# eMMC.net
KiCad netlist of a schematic drawn in Altium Designer
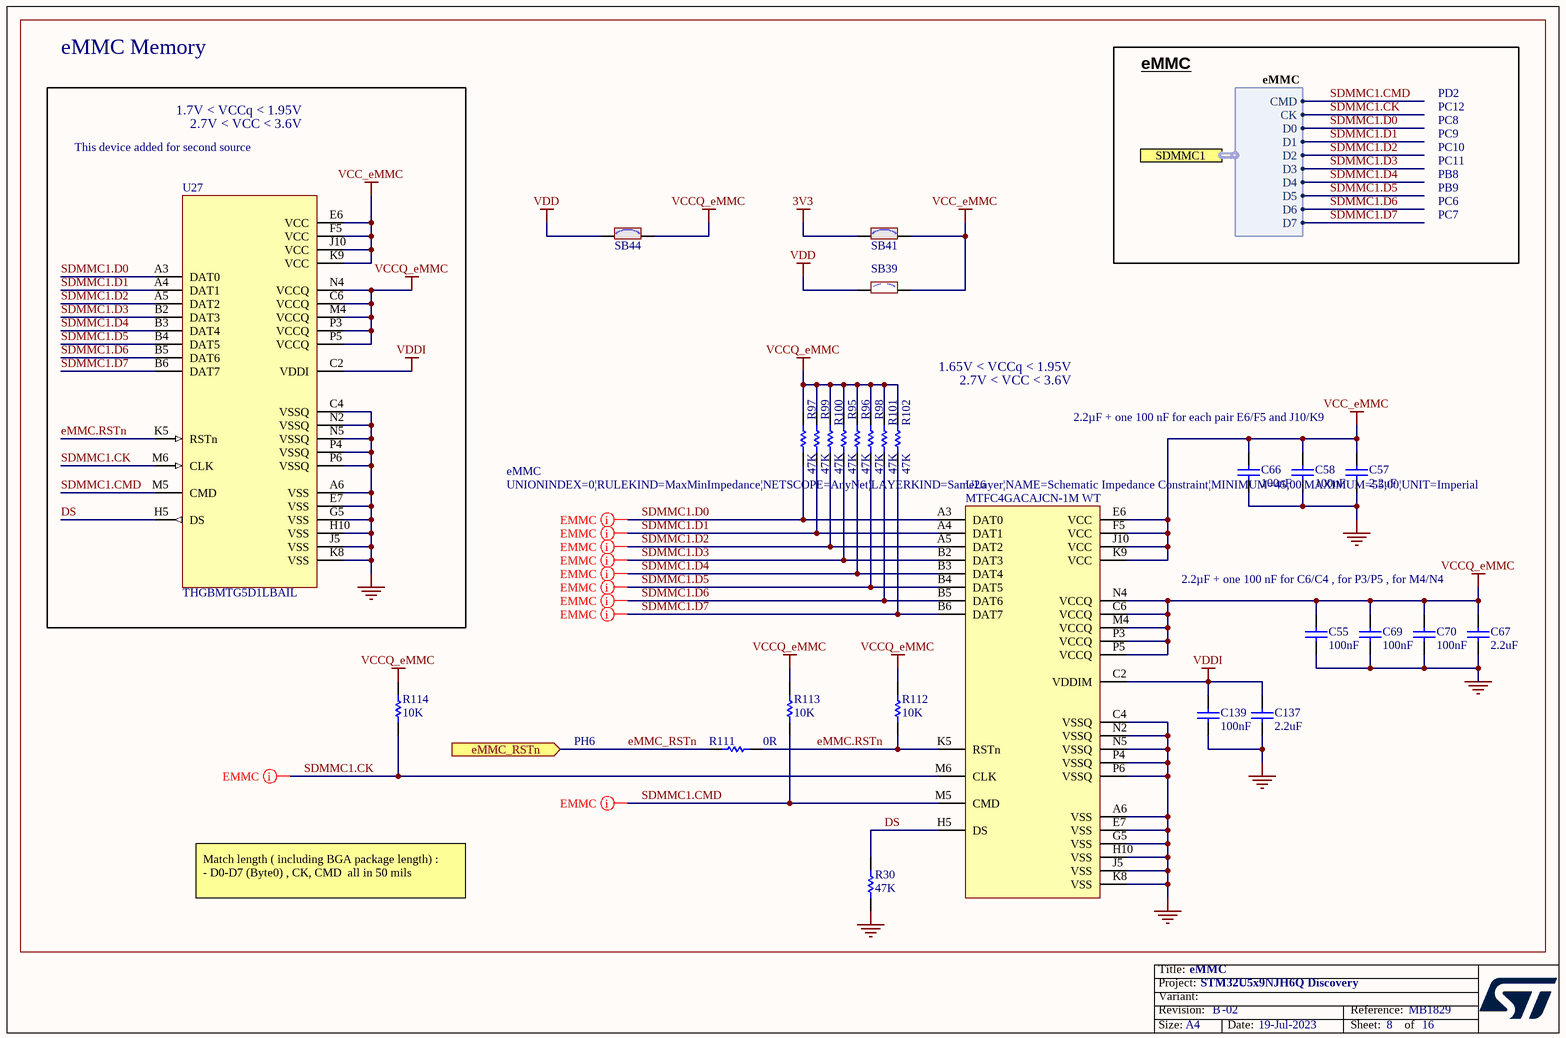
[diagram p0: eMMC.SchDoc]

(export (version "E")
  (design (tool "Eeschema 10.0.6"))
  (components
    (comp (ref "C55")
      (value "100nF")
      (footprint "MCD_PARTS:C0402")
      (description "Capacitor, MLCC, 100nF, 16V, X7R, +/-10%, 0402, T=0.5mm")
      (fields
        (field (name "INTERNAL_PART_NUMBER") "MCD-00006")
        (field (name "MANUFACTURER_PART_NUMBER") "CC0402KRX7R7BB104")
      )
      (libsource (lib "MCD_PARTS_database") (part "Capacitor"))
    )
    (comp (ref "C57")
      (value "2.2uF")
      (footprint "MCD_PARTS:C0603")
      (description "Capacitor, MLCC, 2.2uF, 10V, X5R, +/- 10%, 0603, T=0.8mm")
      (fields
        (field (name "INTERNAL_PART_NUMBER") "MCD-00012")
        (field (name "MANUFACTURER_PART_NUMBER") "CC0603KRX5R6BB225")
      )
      (libsource (lib "MCD_PARTS_database") (part "Capacitor"))
    )
    (comp (ref "C58")
      (value "100nF")
      (footprint "MCD_PARTS:C0402")
      (description "Capacitor, MLCC, 100nF, 16V, X7R, +/-10%, 0402, T=0.5mm")
      (fields
        (field (name "INTERNAL_PART_NUMBER") "MCD-00006")
        (field (name "MANUFACTURER_PART_NUMBER") "CC0402KRX7R7BB104")
      )
      (libsource (lib "MCD_PARTS_database") (part "Capacitor"))
    )
    (comp (ref "C66")
      (value "100nF")
      (footprint "MCD_PARTS:C0402")
      (description "Capacitor, MLCC, 100nF, 16V, X7R, +/-10%, 0402, T=0.5mm")
      (fields
        (field (name "INTERNAL_PART_NUMBER") "MCD-00006")
        (field (name "MANUFACTURER_PART_NUMBER") "CC0402KRX7R7BB104")
      )
      (libsource (lib "MCD_PARTS_database") (part "Capacitor"))
    )
    (comp (ref "C67")
      (value "2.2uF")
      (footprint "MCD_PARTS:C0603")
      (description "Capacitor, MLCC, 2.2uF, 10V, X5R, +/- 10%, 0603, T=0.8mm")
      (fields
        (field (name "INTERNAL_PART_NUMBER") "MCD-00012")
        (field (name "MANUFACTURER_PART_NUMBER") "CC0603KRX5R6BB225")
      )
      (libsource (lib "MCD_PARTS_database") (part "Capacitor"))
    )
    (comp (ref "C69")
      (value "100nF")
      (footprint "MCD_PARTS:C0402")
      (description "Capacitor, MLCC, 100nF, 16V, X7R, +/-10%, 0402, T=0.5mm")
      (fields
        (field (name "INTERNAL_PART_NUMBER") "MCD-00006")
        (field (name "MANUFACTURER_PART_NUMBER") "CC0402KRX7R7BB104")
      )
      (libsource (lib "MCD_PARTS_database") (part "Capacitor"))
    )
    (comp (ref "C70")
      (value "100nF")
      (footprint "MCD_PARTS:C0402")
      (description "Capacitor, MLCC, 100nF, 16V, X7R, +/-10%, 0402, T=0.5mm")
      (fields
        (field (name "INTERNAL_PART_NUMBER") "MCD-00006")
        (field (name "MANUFACTURER_PART_NUMBER") "CC0402KRX7R7BB104")
      )
      (libsource (lib "MCD_PARTS_database") (part "Capacitor"))
    )
    (comp (ref "C137")
      (value "2.2uF")
      (footprint "MCD_PARTS:C0603")
      (description "Capacitor, MLCC, 2.2uF, 10V, X5R, +/- 10%, 0603, T=0.8mm")
      (fields
        (field (name "INTERNAL_PART_NUMBER") "MCD-00012")
        (field (name "MANUFACTURER_PART_NUMBER") "CC0603KRX5R6BB225")
      )
      (libsource (lib "MCD_PARTS_database") (part "Capacitor"))
    )
    (comp (ref "C139")
      (value "100nF")
      (footprint "MCD_PARTS:C0402")
      (description "Capacitor, MLCC, 100nF, 16V, X7R, +/-10%, 0402, T=0.5mm")
      (fields
        (field (name "INTERNAL_PART_NUMBER") "MCD-00006")
        (field (name "MANUFACTURER_PART_NUMBER") "CC0402KRX7R7BB104")
      )
      (libsource (lib "MCD_PARTS_database") (part "Capacitor"))
    )
    (comp (ref "R30")
      (value "47K")
      (footprint "MCD_PARTS:R0402")
      (description "Resistor, 47K, 0402, +/-1%, 1/16W")
      (fields
        (field (name "INTERNAL_PART_NUMBER") "MCD-00063")
        (field (name "MANUFACTURER_PART_NUMBER") "RC0402FR-0747KL")
      )
      (libsource (lib "MCD_PARTS_database") (part "Resistor"))
    )
    (comp (ref "R95")
      (value "47K")
      (footprint "MCD_PARTS:R0402")
      (description "Resistor, 47K, 0402, +/-1%, 1/16W")
      (fields
        (field (name "INTERNAL_PART_NUMBER") "MCD-00063")
        (field (name "MANUFACTURER_PART_NUMBER") "RC0402FR-0747KL")
      )
      (libsource (lib "MCD_PARTS_database") (part "Resistor"))
    )
    (comp (ref "R96")
      (value "47K")
      (footprint "MCD_PARTS:R0402")
      (description "Resistor, 47K, 0402, +/-1%, 1/16W")
      (fields
        (field (name "INTERNAL_PART_NUMBER") "MCD-00063")
        (field (name "MANUFACTURER_PART_NUMBER") "RC0402FR-0747KL")
      )
      (libsource (lib "MCD_PARTS_database") (part "Resistor"))
    )
    (comp (ref "R97")
      (value "47K")
      (footprint "MCD_PARTS:R0402")
      (description "Resistor, 47K, 0402, +/-1%, 1/16W")
      (fields
        (field (name "INTERNAL_PART_NUMBER") "MCD-00063")
        (field (name "MANUFACTURER_PART_NUMBER") "RC0402FR-0747KL")
      )
      (libsource (lib "MCD_PARTS_database") (part "Resistor"))
    )
    (comp (ref "R98")
      (value "47K")
      (footprint "MCD_PARTS:R0402")
      (description "Resistor, 47K, 0402, +/-1%, 1/16W")
      (fields
        (field (name "INTERNAL_PART_NUMBER") "MCD-00063")
        (field (name "MANUFACTURER_PART_NUMBER") "RC0402FR-0747KL")
      )
      (libsource (lib "MCD_PARTS_database") (part "Resistor"))
    )
    (comp (ref "R99")
      (value "47K")
      (footprint "MCD_PARTS:R0402")
      (description "Resistor, 47K, 0402, +/-1%, 1/16W")
      (fields
        (field (name "INTERNAL_PART_NUMBER") "MCD-00063")
        (field (name "MANUFACTURER_PART_NUMBER") "RC0402FR-0747KL")
      )
      (libsource (lib "MCD_PARTS_database") (part "Resistor"))
    )
    (comp (ref "R100")
      (value "47K")
      (footprint "MCD_PARTS:R0402")
      (description "Resistor, 47K, 0402, +/-1%, 1/16W")
      (fields
        (field (name "INTERNAL_PART_NUMBER") "MCD-00063")
        (field (name "MANUFACTURER_PART_NUMBER") "RC0402FR-0747KL")
      )
      (libsource (lib "MCD_PARTS_database") (part "Resistor"))
    )
    (comp (ref "R101")
      (value "47K")
      (footprint "MCD_PARTS:R0402")
      (description "Resistor, 47K, 0402, +/-1%, 1/16W")
      (fields
        (field (name "INTERNAL_PART_NUMBER") "MCD-00063")
        (field (name "MANUFACTURER_PART_NUMBER") "RC0402FR-0747KL")
      )
      (libsource (lib "MCD_PARTS_database") (part "Resistor"))
    )
    (comp (ref "R102")
      (value "47K")
      (footprint "MCD_PARTS:R0402")
      (description "Resistor, 47K, 0402, +/-1%, 1/16W")
      (fields
        (field (name "INTERNAL_PART_NUMBER") "MCD-00063")
        (field (name "MANUFACTURER_PART_NUMBER") "RC0402FR-0747KL")
      )
      (libsource (lib "MCD_PARTS_database") (part "Resistor"))
    )
    (comp (ref "R111")
      (value "0R")
      (footprint "MCD_PARTS:R0402")
      (description "Resistor, 0R, 0402, +/-5%, 1/16W")
      (fields
        (field (name "INTERNAL_PART_NUMBER") "MCD-00052")
        (field (name "MANUFACTURER_PART_NUMBER") "RC0402JR-070RL")
      )
      (libsource (lib "MCD_PARTS_database") (part "Resistor"))
    )
    (comp (ref "R112")
      (value "10K")
      (footprint "MCD_PARTS:R0402")
      (description "Resistor, 10K, 0402, +/-1%, 1/16W")
      (fields
        (field (name "INTERNAL_PART_NUMBER") "MCD-00053")
        (field (name "MANUFACTURER_PART_NUMBER") "RC0402FR-0710KL")
      )
      (libsource (lib "MCD_PARTS_database") (part "Resistor"))
    )
    (comp (ref "R113")
      (value "10K")
      (footprint "MCD_PARTS:R0402")
      (description "Resistor, 10K, 0402, +/-1%, 1/16W")
      (fields
        (field (name "INTERNAL_PART_NUMBER") "MCD-00053")
        (field (name "MANUFACTURER_PART_NUMBER") "RC0402FR-0710KL")
      )
      (libsource (lib "MCD_PARTS_database") (part "Resistor"))
    )
    (comp (ref "R114")
      (value "10K")
      (footprint "MCD_PARTS:R0402")
      (description "Resistor, 10K, 0402, +/-1%, 1/16W")
      (fields
        (field (name "INTERNAL_PART_NUMBER") "MCD-00053")
        (field (name "MANUFACTURER_PART_NUMBER") "RC0402FR-0710KL")
      )
      (libsource (lib "MCD_PARTS_database") (part "Resistor"))
    )
    (comp (ref "SB39")
      (value "SB_OFF")
      (footprint "MCD_PARTS:SOLDER-BRIDGE_R0402-0R")
      (description "Solder Bridge 0402 OFF")
      (fields
        (field (name "INTERNAL_PART_NUMBER") "MCD-02162")
        (field (name "MANUFACTURER_PART_NUMBER") "RC0402JR-070RL")
      )
      (libsource (lib "MCD_PARTS_database") (part "SB_OFF"))
    )
    (comp (ref "SB41")
      (value "SB_ON")
      (footprint "MCD_PARTS:SOLDER-BRIDGE_R0402-0R")
      (description "Solder Bridge 0402 ON")
      (fields
        (field (name "INTERNAL_PART_NUMBER") "MCD-01618")
        (field (name "MANUFACTURER_PART_NUMBER") "RC0402JR-070RL")
      )
      (libsource (lib "MCD_PARTS_database") (part "SB_ON"))
    )
    (comp (ref "SB44")
      (value "SB_ON")
      (footprint "MCD_PARTS:SOLDER-BRIDGE_R0402-0R")
      (description "Solder Bridge 0402 ON")
      (fields
        (field (name "INTERNAL_PART_NUMBER") "MCD-01618")
        (field (name "MANUFACTURER_PART_NUMBER") "RC0402JR-070RL")
      )
      (libsource (lib "MCD_PARTS_database") (part "SB_ON"))
    )
    (comp (ref "U26")
      (value "MTFC4GACAJCN-1M WT")
      (footprint "MCD_PARTS:ICC_P-WFBGA153_13X11P5_P050")
      (description "4G MultiMediaCard (MMC) controller and NAND Flash")
      (fields (field (name "INTERNAL_PART_NUMBER") "MCD-01137") (field (name "MANUFACTURER") "MICRON"))
      (libsource (lib "MCD_PARTS_database") (part "MTFC4GACAJCN-1M WT"))
    )
    (comp (ref "U27")
      (value "THGBMTG5D1LBAIL")
      (footprint "MCD_PARTS:ICC_P-WFBGA153_13X11P5_P050")
      (description "Memory, eMMC, 4GB, 15nm ,WFBGA , 153 pins")
      (fields (field (name "INTERNAL_PART_NUMBER") "MCD-02799") (field (name "MANUFACTURER") "KIOXIA"))
      (libsource (lib "MCD_PARTS_database") (part "eMMC_THGBMTG5D1LBAIL"))
    )
  )
  (nets
    (net (code "2") (name "/DS") (class "Default")
      (node (ref "R30") (pin "2") (pinfunction "2_2") (pintype "passive"))
      (node (ref "U26") (pin "H5") (pinfunction "DS_H5") (pintype "passive"))
      (node (ref "U27") (pin "H5") (pinfunction "DS_H5") (pintype "output"))
    )
    (net (code "3") (name "/SDMMC1.CK") (class "Default")
      (node (ref "R114") (pin "1") (pinfunction "1_1") (pintype "passive"))
      (node (ref "U26") (pin "M6") (pinfunction "CLK_M6") (pintype "passive"))
      (node (ref "U27") (pin "M6") (pinfunction "CLK_M6") (pintype "input"))
    )
    (net (code "4") (name "/SDMMC1.CMD") (class "Default")
      (node (ref "R113") (pin "1") (pinfunction "1_1") (pintype "passive"))
      (node (ref "U26") (pin "M5") (pinfunction "CMD_M5") (pintype "passive"))
      (node (ref "U27") (pin "M5") (pinfunction "CMD_M5") (pintype "passive"))
    )
    (net (code "5") (name "/SDMMC1.D0") (class "Default")
      (node (ref "R97") (pin "1") (pinfunction "1_1") (pintype "passive"))
      (node (ref "U26") (pin "A3") (pinfunction "DAT0_A3") (pintype "passive"))
      (node (ref "U27") (pin "A3") (pinfunction "DAT0_A3") (pintype "passive"))
    )
    (net (code "6") (name "/SDMMC1.D1") (class "Default")
      (node (ref "R99") (pin "1") (pinfunction "1_1") (pintype "passive"))
      (node (ref "U26") (pin "A4") (pinfunction "DAT1_A4") (pintype "passive"))
      (node (ref "U27") (pin "A4") (pinfunction "DAT1_A4") (pintype "passive"))
    )
    (net (code "7") (name "/SDMMC1.D2") (class "Default")
      (node (ref "R100") (pin "1") (pinfunction "1_1") (pintype "passive"))
      (node (ref "U26") (pin "A5") (pinfunction "DAT2_A5") (pintype "passive"))
      (node (ref "U27") (pin "A5") (pinfunction "DAT2_A5") (pintype "passive"))
    )
    (net (code "8") (name "/SDMMC1.D3") (class "Default")
      (node (ref "R95") (pin "1") (pinfunction "1_1") (pintype "passive"))
      (node (ref "U26") (pin "B2") (pinfunction "DAT3_B2") (pintype "passive"))
      (node (ref "U27") (pin "B2") (pinfunction "DAT3_B2") (pintype "passive"))
    )
    (net (code "9") (name "/SDMMC1.D4") (class "Default")
      (node (ref "R96") (pin "1") (pinfunction "1_1") (pintype "passive"))
      (node (ref "U26") (pin "B3") (pinfunction "DAT4_B3") (pintype "passive"))
      (node (ref "U27") (pin "B3") (pinfunction "DAT4_B3") (pintype "passive"))
    )
    (net (code "10") (name "/SDMMC1.D5") (class "Default")
      (node (ref "R98") (pin "1") (pinfunction "1_1") (pintype "passive"))
      (node (ref "U26") (pin "B4") (pinfunction "DAT5_B4") (pintype "passive"))
      (node (ref "U27") (pin "B4") (pinfunction "DAT5_B4") (pintype "passive"))
    )
    (net (code "11") (name "/SDMMC1.D6") (class "Default")
      (node (ref "R101") (pin "1") (pinfunction "1_1") (pintype "passive"))
      (node (ref "U26") (pin "B5") (pinfunction "DAT6_B5") (pintype "passive"))
      (node (ref "U27") (pin "B5") (pinfunction "DAT6_B5") (pintype "passive"))
    )
    (net (code "12") (name "/SDMMC1.D7") (class "Default")
      (node (ref "R102") (pin "1") (pinfunction "1_1") (pintype "passive"))
      (node (ref "U26") (pin "B6") (pinfunction "DAT7_B6") (pintype "passive"))
      (node (ref "U27") (pin "B6") (pinfunction "DAT7_B6") (pintype "passive"))
    )
    (net (code "13") (name "/eMMC.RSTn") (class "Default")
      (node (ref "R111") (pin "2") (pinfunction "2_2") (pintype "passive"))
      (node (ref "R112") (pin "1") (pinfunction "1_1") (pintype "passive"))
      (node (ref "U26") (pin "K5") (pinfunction "RSTn_K5") (pintype "passive"))
      (node (ref "U27") (pin "K5") (pinfunction "RSTn_K5") (pintype "input"))
    )
    (net (code "14") (name "/eMMC_RSTn") (class "Default")
      (node (ref "R111") (pin "1") (pinfunction "1_1") (pintype "passive"))
    )
    (net (code "16") (name "3V3") (class "Default")
      (node (ref "SB41") (pin "1") (pinfunction "1_1") (pintype "passive"))
    )
    (net (code "17") (name "GND") (class "Default")
      (node (ref "C137") (pin "1") (pinfunction "1_1") (pintype "passive"))
      (node (ref "C139") (pin "1") (pinfunction "1_1") (pintype "passive"))
      (node (ref "C55") (pin "1") (pinfunction "1_1") (pintype "passive"))
      (node (ref "C57") (pin "1") (pinfunction "1_1") (pintype "passive"))
      (node (ref "C58") (pin "1") (pinfunction "1_1") (pintype "passive"))
      (node (ref "C66") (pin "1") (pinfunction "1_1") (pintype "passive"))
      (node (ref "C67") (pin "1") (pinfunction "1_1") (pintype "passive"))
      (node (ref "C69") (pin "1") (pinfunction "1_1") (pintype "passive"))
      (node (ref "C70") (pin "1") (pinfunction "1_1") (pintype "passive"))
      (node (ref "R30") (pin "1") (pinfunction "1_1") (pintype "passive"))
      (node (ref "U26") (pin "A6") (pinfunction "VSS_A6") (pintype "passive"))
      (node (ref "U26") (pin "C4") (pinfunction "VSSQ_C4") (pintype "passive"))
      (node (ref "U26") (pin "E7") (pinfunction "VSS_E7") (pintype "passive"))
      (node (ref "U26") (pin "G5") (pinfunction "VSS_G5") (pintype "passive"))
      (node (ref "U26") (pin "H10") (pinfunction "VSS_H10") (pintype "passive"))
      (node (ref "U26") (pin "J5") (pinfunction "VSS_J5") (pintype "passive"))
      (node (ref "U26") (pin "K8") (pinfunction "VSS_K8") (pintype "passive"))
      (node (ref "U26") (pin "N2") (pinfunction "VSSQ_N2") (pintype "passive"))
      (node (ref "U26") (pin "N5") (pinfunction "VSSQ_N5") (pintype "passive"))
      (node (ref "U26") (pin "P4") (pinfunction "VSSQ_P4") (pintype "passive"))
      (node (ref "U26") (pin "P6") (pinfunction "VSSQ_P6") (pintype "passive"))
      (node (ref "U27") (pin "A6") (pinfunction "VSS_A6") (pintype "passive"))
      (node (ref "U27") (pin "C4") (pinfunction "VSSQ_C4") (pintype "passive"))
      (node (ref "U27") (pin "E7") (pinfunction "VSS_E7") (pintype "passive"))
      (node (ref "U27") (pin "G5") (pinfunction "VSS_G5") (pintype "passive"))
      (node (ref "U27") (pin "H10") (pinfunction "VSS_H10") (pintype "passive"))
      (node (ref "U27") (pin "J5") (pinfunction "VSS_J5") (pintype "passive"))
      (node (ref "U27") (pin "K8") (pinfunction "VSS_K8") (pintype "passive"))
      (node (ref "U27") (pin "N2") (pinfunction "VSSQ_N2") (pintype "passive"))
      (node (ref "U27") (pin "N5") (pinfunction "VSSQ_N5") (pintype "passive"))
      (node (ref "U27") (pin "P4") (pinfunction "VSSQ_P4") (pintype "passive"))
      (node (ref "U27") (pin "P6") (pinfunction "VSSQ_P6") (pintype "passive"))
    )
    (net (code "18") (name "VCCQ_eMMC") (class "Default")
      (node (ref "C55") (pin "2") (pinfunction "2_2") (pintype "passive"))
      (node (ref "C67") (pin "2") (pinfunction "2_2") (pintype "passive"))
      (node (ref "C69") (pin "2") (pinfunction "2_2") (pintype "passive"))
      (node (ref "C70") (pin "2") (pinfunction "2_2") (pintype "passive"))
      (node (ref "R100") (pin "2") (pinfunction "2_2") (pintype "passive"))
      (node (ref "R101") (pin "2") (pinfunction "2_2") (pintype "passive"))
      (node (ref "R102") (pin "2") (pinfunction "2_2") (pintype "passive"))
      (node (ref "R112") (pin "2") (pinfunction "2_2") (pintype "passive"))
      (node (ref "R113") (pin "2") (pinfunction "2_2") (pintype "passive"))
      (node (ref "R114") (pin "2") (pinfunction "2_2") (pintype "passive"))
      (node (ref "R95") (pin "2") (pinfunction "2_2") (pintype "passive"))
      (node (ref "R96") (pin "2") (pinfunction "2_2") (pintype "passive"))
      (node (ref "R97") (pin "2") (pinfunction "2_2") (pintype "passive"))
      (node (ref "R98") (pin "2") (pinfunction "2_2") (pintype "passive"))
      (node (ref "R99") (pin "2") (pinfunction "2_2") (pintype "passive"))
      (node (ref "SB44") (pin "2") (pinfunction "2_2") (pintype "passive"))
      (node (ref "U26") (pin "C6") (pinfunction "VCCQ_C6") (pintype "passive"))
      (node (ref "U26") (pin "M4") (pinfunction "VCCQ_M4") (pintype "passive"))
      (node (ref "U26") (pin "N4") (pinfunction "VCCQ_N4") (pintype "passive"))
      (node (ref "U26") (pin "P3") (pinfunction "VCCQ_P3") (pintype "passive"))
      (node (ref "U26") (pin "P5") (pinfunction "VCCQ_P5") (pintype "passive"))
      (node (ref "U27") (pin "C6") (pinfunction "VCCQ_C6") (pintype "passive"))
      (node (ref "U27") (pin "M4") (pinfunction "VCCQ_M4") (pintype "passive"))
      (node (ref "U27") (pin "N4") (pinfunction "VCCQ_N4") (pintype "passive"))
      (node (ref "U27") (pin "P3") (pinfunction "VCCQ_P3") (pintype "passive"))
      (node (ref "U27") (pin "P5") (pinfunction "VCCQ_P5") (pintype "passive"))
    )
    (net (code "19") (name "VCC_eMMC") (class "Default")
      (node (ref "C57") (pin "2") (pinfunction "2_2") (pintype "passive"))
      (node (ref "C58") (pin "2") (pinfunction "2_2") (pintype "passive"))
      (node (ref "C66") (pin "2") (pinfunction "2_2") (pintype "passive"))
      (node (ref "SB39") (pin "2") (pinfunction "2_2") (pintype "passive"))
      (node (ref "SB41") (pin "2") (pinfunction "2_2") (pintype "passive"))
      (node (ref "U26") (pin "E6") (pinfunction "VCC_E6") (pintype "passive"))
      (node (ref "U26") (pin "F5") (pinfunction "VCC_F5") (pintype "passive"))
      (node (ref "U26") (pin "J10") (pinfunction "VCC_J10") (pintype "passive"))
      (node (ref "U26") (pin "K9") (pinfunction "VCC_K9") (pintype "passive"))
      (node (ref "U27") (pin "E6") (pinfunction "VCC_E6") (pintype "passive"))
      (node (ref "U27") (pin "F5") (pinfunction "VCC_F5") (pintype "passive"))
      (node (ref "U27") (pin "J10") (pinfunction "VCC_J10") (pintype "passive"))
      (node (ref "U27") (pin "K9") (pinfunction "VCC_K9") (pintype "passive"))
    )
    (net (code "20") (name "VDD") (class "Default")
      (node (ref "SB39") (pin "1") (pinfunction "1_1") (pintype "passive"))
      (node (ref "SB44") (pin "1") (pinfunction "1_1") (pintype "passive"))
    )
    (net (code "21") (name "VDDI") (class "Default")
      (node (ref "C137") (pin "2") (pinfunction "2_2") (pintype "passive"))
      (node (ref "C139") (pin "2") (pinfunction "2_2") (pintype "passive"))
      (node (ref "U26") (pin "C2") (pinfunction "VDDIM_C2") (pintype "passive"))
      (node (ref "U27") (pin "C2") (pinfunction "VDDI_C2") (pintype "passive"))
    )
  )
)
